# helium.net
KiCad netlist of a schematic drawn in EAGLE
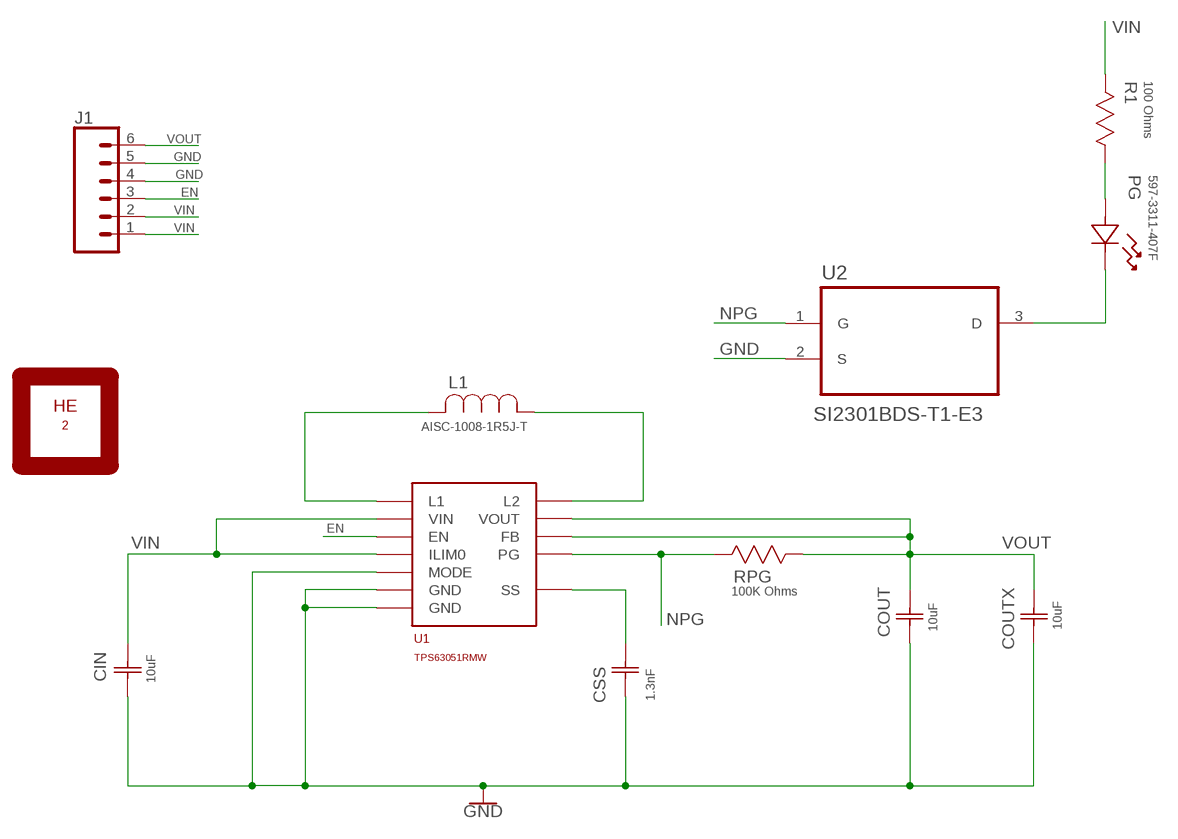
[diagram p0: schematic, sheet 1]

(export (version "E")
  (design (tool "Eeschema 10.0.6"))
  (components
    (comp (ref "CIN")
      (value "10uF")
      (footprint "eagle-import:CAPC1608X85N")
      (fields (field (name "MPN") "GRM188R60J106ME47D ") (field (name "TOLERANCE") "±20%"))
      (libsource (lib "eagle-import") (part "GRM188R60J106ME47D"))
    )
    (comp (ref "COUT")
      (value "10uF")
      (footprint "eagle-import:CAPC1608X85N")
      (fields (field (name "MPN") "GRM188R60J106ME47D ") (field (name "TOLERANCE") "±20%"))
      (libsource (lib "eagle-import") (part "GRM188R60J106ME47D"))
    )
    (comp (ref "COUTX")
      (value "10uF")
      (footprint "eagle-import:CAPC1608X85N")
      (fields (field (name "MPN") "GRM188R60J106ME47D ") (field (name "TOLERANCE") "±20%"))
      (libsource (lib "eagle-import") (part "GRM188R60J106ME47D"))
    )
    (comp (ref "CSS")
      (value "1.3nF")
      (footprint "eagle-import:CAPC1005X60N")
      (fields (field (name "MPN") "C0402C132J5GACTU") (field (name "TOLERANCE") "±5%"))
      (libsource (lib "eagle-import") (part "C0402C132J5GACTU"))
    )
    (comp (ref "HE")
      (value "2")
      (footprint "eagle-import:PERIODIC_SYMBOL_BACK")
      (fields (field (name "DESC") "rev.0"))
      (libsource (lib "eagle-import") (part "PERIODIC_SYMBOL"))
    )
    (comp (ref "J1")
      (value "CONN_06LONGPADS")
      (footprint "eagle-import:1X06_LONGPADS")
      (libsource (lib "eagle-import") (part "CONN_06LONGPADS"))
    )
    (comp (ref "L1")
      (value "AISC-1008-1R5J-T")
      (footprint "eagle-import:AISC-1008")
      (fields (field (name "MANUFACTURER_PART_NUMBER") "AISC10081R5JT"))
      (libsource (lib "eagle-import") (part "AISC-1008-1R5J-T"))
    )
    (comp (ref "PG")
      (value "597-3311-407F")
      (footprint "eagle-import:LED_597-3311-407F")
      (libsource (lib "eagle-import") (part "597-3311-407F"))
    )
    (comp (ref "R1")
      (value "100 Ohms")
      (footprint "eagle-import:RESC1005X40N")
      (fields (field (name "MPN") "9C04021A1000FLHF3") (field (name "TOLERANCE") "±1%"))
      (libsource (lib "eagle-import") (part "9C04021A1000FLHF3"))
    )
    (comp (ref "RPG")
      (value "100K Ohms")
      (footprint "eagle-import:RESC1608X60N")
      (fields (field (name "MPN") "CRCW0603100KFKEA") (field (name "TOLERANCE") "± 1.0 %"))
      (libsource (lib "eagle-import") (part "CRCW0603100KFKEA"))
    )
    (comp (ref "U1")
      (value "TPS63051RMW")
      (footprint "eagle-import:RMW12")
      (libsource (lib "eagle-import") (part "TPS6305X"))
    )
    (comp (ref "U2")
      (value "SI2301BDS-T1-E3")
      (footprint "eagle-import:SOT95P237X112-3N")
      (libsource (lib "eagle-import") (part "SI2301BDS-T1-E3"))
    )
  )
  (nets
    (net (code "1") (name "/EN") (class "Default")
      (node (ref "J1") (pin "3") (pinfunction "3_3") (pintype "passive"))
      (node (ref "U1") (pin "P$11") (pinfunction "EN_P$11") (pintype "input"))
    )
    (net (code "2") (name "/NPG") (class "Default")
      (node (ref "RPG") (pin "2") (pinfunction "2_2") (pintype "passive"))
      (node (ref "U1") (pin "P$8") (pinfunction "PG_P$8") (pintype "open_collector"))
      (node (ref "U2") (pin "1") (pinfunction "G_1") (pintype "passive"))
    )
    (net (code "3") (name "/VIN") (class "Default")
      (node (ref "CIN") (pin "2") (pinfunction "C2_2") (pintype "passive"))
      (node (ref "J1") (pin "1") (pinfunction ">NAME_1") (pintype "passive"))
      (node (ref "J1") (pin "2") (pinfunction "2_2") (pintype "passive"))
      (node (ref "R1") (pin "2") (pinfunction "R2_2") (pintype "passive"))
      (node (ref "U1") (pin "P$10") (pinfunction "ILIM0_P$10") (pintype "input"))
      (node (ref "U1") (pin "P$12") (pinfunction "VIN_P$12") (pintype "power_in"))
    )
    (net (code "4") (name "/VOUT") (class "Default")
      (node (ref "COUT") (pin "2") (pinfunction "C2_2") (pintype "passive"))
      (node (ref "COUTX") (pin "2") (pinfunction "C2_2") (pintype "passive"))
      (node (ref "J1") (pin "6") (pinfunction "6_6") (pintype "passive"))
      (node (ref "RPG") (pin "1") (pinfunction "1_1") (pintype "passive"))
      (node (ref "U1") (pin "P$4") (pinfunction "VOUT_P$4") (pintype "power_in"))
      (node (ref "U1") (pin "P$5") (pinfunction "FB_P$5") (pintype "input"))
    )
    (net (code "5") (name "GND") (class "Default")
      (node (ref "CIN") (pin "1") (pinfunction "C1_1") (pintype "passive"))
      (node (ref "COUT") (pin "1") (pinfunction "C1_1") (pintype "passive"))
      (node (ref "COUTX") (pin "1") (pinfunction "C1_1") (pintype "passive"))
      (node (ref "CSS") (pin "1") (pinfunction "C1_1") (pintype "passive"))
      (node (ref "J1") (pin "4") (pinfunction "4_4") (pintype "passive"))
      (node (ref "J1") (pin "5") (pinfunction "5_5") (pintype "passive"))
      (node (ref "U1") (pin "P$2") (pinfunction "GND_P$2") (pintype "power_in"))
      (node (ref "U1") (pin "P$6") (pinfunction "MODE_P$6") (pintype "input"))
      (node (ref "U1") (pin "P$9") (pinfunction "GND_P$9") (pintype "power_in"))
      (node (ref "U2") (pin "2") (pinfunction "S_2") (pintype "passive"))
    )
    (net (code "6") (name "Net-(CSS-C2)") (class "Default")
      (node (ref "CSS") (pin "2") (pinfunction "C2_2") (pintype "passive"))
      (node (ref "U1") (pin "P$7") (pinfunction "SS_P$7") (pintype "input"))
    )
    (net (code "7") (name "Net-(R1-R1)") (class "Default")
      (node (ref "PG") (pin "2") (pinfunction "2_2") (pintype "passive"))
      (node (ref "R1") (pin "1") (pinfunction "R1_1") (pintype "passive"))
    )
    (net (code "8") (name "Net-(U1-L1)") (class "Default")
      (node (ref "L1") (pin "2") (pinfunction "2_2") (pintype "passive"))
      (node (ref "U1") (pin "P$1") (pinfunction "L1_P$1") (pintype "passive"))
    )
    (net (code "9") (name "Net-(U1-L2)") (class "Default")
      (node (ref "L1") (pin "1") (pinfunction "1_1") (pintype "passive"))
      (node (ref "U1") (pin "P$3") (pinfunction "L2_P$3") (pintype "passive"))
    )
    (net (code "10") (name "Net-(U2-D)") (class "Default")
      (node (ref "PG") (pin "1") (pinfunction "1_1") (pintype "passive"))
      (node (ref "U2") (pin "3") (pinfunction "D_3") (pintype "passive"))
    )
  )
)
